# Advertisement_Matrix.net
KiCad netlist of a schematic drawn in EAGLE
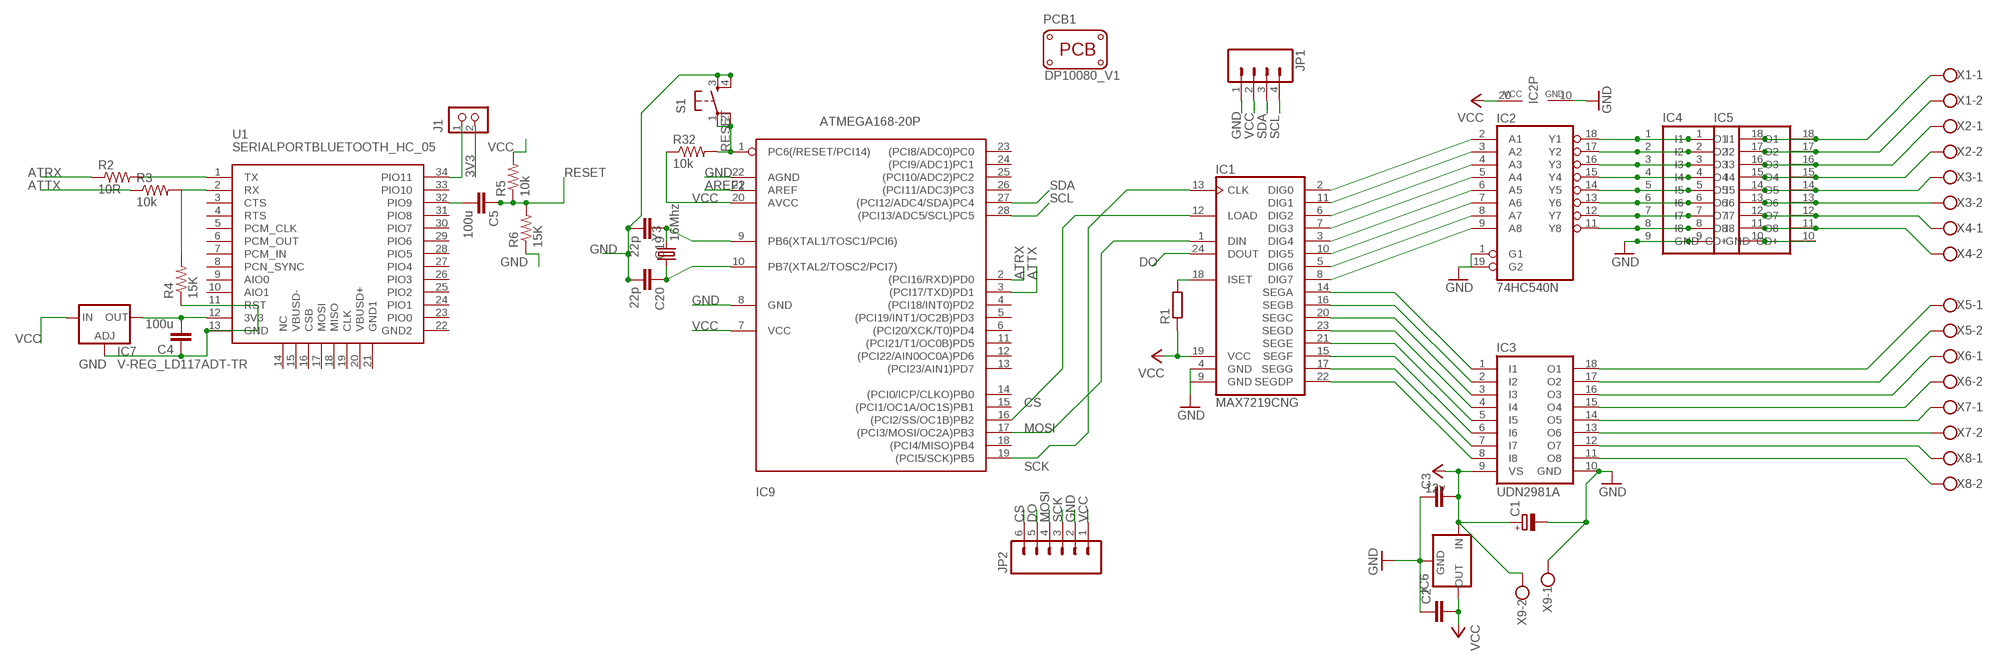
[diagram p0: schematic, sheet 1]

(export (version "E")
  (design (tool "Eeschema 10.0.6"))
  (components
    (comp (ref "C1")
      (value "CPOL-EUE2.5-7")
      (footprint "eagle-import:E2,5-7")
      (libsource (lib "eagle-import") (part "CPOL-EUE2.5-7"))
    )
    (comp (ref "C2")
      (value "C-EUC1206K")
      (footprint "eagle-import:C1206K")
      (libsource (lib "eagle-import") (part "C-EUC1206K"))
    )
    (comp (ref "C3")
      (value "C-EUC1206K")
      (footprint "eagle-import:C1206K")
      (libsource (lib "eagle-import") (part "C-EUC1206K"))
    )
    (comp (ref "C4")
      (value "100u")
      (footprint "eagle-import:1206")
      (libsource (lib "eagle-import") (part "CAP1206"))
    )
    (comp (ref "C5")
      (value "100u")
      (footprint "eagle-import:1206")
      (libsource (lib "eagle-import") (part "CAP1206"))
    )
    (comp (ref "C19")
      (value "22p")
      (footprint "eagle-import:1206")
      (libsource (lib "eagle-import") (part "CAP1206"))
    )
    (comp (ref "C20")
      (value "22p")
      (footprint "eagle-import:1206")
      (libsource (lib "eagle-import") (part "CAP1206"))
    )
    (comp (ref "IC1")
      (value "MAX7219CNG")
      (footprint "eagle-import:DIL24-3")
      (fields (field (name "MF") "MAXIM"))
      (libsource (lib "eagle-import") (part "MAX7219CNG"))
    )
    (comp (ref "IC2")
      (value "74HC540N")
      (footprint "eagle-import:DIL20")
      (libsource (lib "eagle-import") (part "74540NHC"))
    )
    (comp (ref "IC3")
      (value "UDN2981A")
      (footprint "eagle-import:DIL18")
      (libsource (lib "eagle-import") (part "UDN298A1"))
    )
    (comp (ref "IC4")
      (value "IC_ULN2803AN")
      (footprint "eagle-import:DIL18")
      (libsource (lib "eagle-import") (part "IC_ULN2803AN"))
    )
    (comp (ref "IC5")
      (value "IC_ULN2803AN")
      (footprint "eagle-import:DIL18")
      (libsource (lib "eagle-import") (part "IC_ULN2803AN"))
    )
    (comp (ref "IC6")
      (value "78XXL")
      (footprint "eagle-import:78XXL")
      (libsource (lib "eagle-import") (part "78XXL"))
    )
    (comp (ref "IC7")
      (value "V-REG_LD117ADT-TR")
      (footprint "eagle-import:V-REG_DPACK")
      (libsource (lib "eagle-import") (part "V-REG_LD117A?DT-TR"))
    )
    (comp (ref "IC9")
      (value "ATMEGA168-20P")
      (footprint "eagle-import:DIL28-3")
      (libsource (lib "eagle-import") (part "ATMEGA168P-20"))
    )
    (comp (ref "J1")
      (value "CON_HEADER_1X02-PTH")
      (footprint "eagle-import:M1X2")
      (libsource (lib "eagle-import") (part "CON_HEADER_1X02-PTH"))
    )
    (comp (ref "JP1")
      (value "M04POLAR_LOCK")
      (footprint "eagle-import:MOLEX-1X4_LOCK")
      (libsource (lib "eagle-import") (part "M04POLAR_LOCK"))
    )
    (comp (ref "JP2")
      (value "M06POLAR_LOCK")
      (footprint "eagle-import:MOLEX-1X6_LOCK")
      (libsource (lib "eagle-import") (part "M06POLAR_LOCK"))
    )
    (comp (ref "PCB1")
      (value "PCB_DP_RECTANGLE-80X100")
      (footprint "eagle-import:DP10080_V1")
      (libsource (lib "eagle-import") (part "PCB_DP_RECTANGLE-80X100"))
    )
    (comp (ref "R1")
      (value "R-EU_0207/7")
      (footprint "eagle-import:0207_7")
      (libsource (lib "eagle-import") (part "R-EU_0207/7"))
    )
    (comp (ref "R2")
      (value "10R")
      (footprint "eagle-import:M1206")
      (libsource (lib "eagle-import") (part "R-US_M1206"))
    )
    (comp (ref "R3")
      (value "10k")
      (footprint "eagle-import:M1206")
      (libsource (lib "eagle-import") (part "R-US_M1206"))
    )
    (comp (ref "R4")
      (value "15K")
      (footprint "eagle-import:M1206")
      (libsource (lib "eagle-import") (part "R-US_M1206"))
    )
    (comp (ref "R5")
      (value "10k")
      (footprint "eagle-import:M1206")
      (libsource (lib "eagle-import") (part "R-US_M1206"))
    )
    (comp (ref "R6")
      (value "15K")
      (footprint "eagle-import:M1206")
      (libsource (lib "eagle-import") (part "R-US_M1206"))
    )
    (comp (ref "R32")
      (value "10k")
      (footprint "eagle-import:M1206")
      (libsource (lib "eagle-import") (part "R-US_M1206"))
    )
    (comp (ref "S1")
      (value "TAC_SWITCHPTH")
      (footprint "eagle-import:TACTILE-PTH")
      (libsource (lib "eagle-import") (part "TAC_SWITCHPTH"))
    )
    (comp (ref "U1")
      (value "SERIALPORTBLUETOOTH_HC_05")
      (footprint "eagle-import:SERIALPORTBLUETOOTH_BLUETOOTH_SMD")
      (libsource (lib "eagle-import") (part "SERIALPORTBLUETOOTH_HC_05"))
    )
    (comp (ref "X1")
      (value "W237-102")
      (footprint "eagle-import:W237-102")
      (fields (field (name "MPN") "237-102"))
      (libsource (lib "eagle-import") (part "W237-102"))
    )
    (comp (ref "X2")
      (value "W237-102")
      (footprint "eagle-import:W237-102")
      (fields (field (name "MPN") "237-102"))
      (libsource (lib "eagle-import") (part "W237-102"))
    )
    (comp (ref "X3")
      (value "W237-102")
      (footprint "eagle-import:W237-102")
      (fields (field (name "MPN") "237-102"))
      (libsource (lib "eagle-import") (part "W237-102"))
    )
    (comp (ref "X4")
      (value "W237-102")
      (footprint "eagle-import:W237-102")
      (fields (field (name "MPN") "237-102"))
      (libsource (lib "eagle-import") (part "W237-102"))
    )
    (comp (ref "X5")
      (value "W237-102")
      (footprint "eagle-import:W237-102")
      (fields (field (name "MPN") "237-102"))
      (libsource (lib "eagle-import") (part "W237-102"))
    )
    (comp (ref "X6")
      (value "W237-102")
      (footprint "eagle-import:W237-102")
      (fields (field (name "MPN") "237-102"))
      (libsource (lib "eagle-import") (part "W237-102"))
    )
    (comp (ref "X7")
      (value "W237-102")
      (footprint "eagle-import:W237-102")
      (fields (field (name "MPN") "237-102"))
      (libsource (lib "eagle-import") (part "W237-102"))
    )
    (comp (ref "X8")
      (value "W237-102")
      (footprint "eagle-import:W237-102")
      (fields (field (name "MPN") "237-102"))
      (libsource (lib "eagle-import") (part "W237-102"))
    )
    (comp (ref "X9")
      (value "W237-102")
      (footprint "eagle-import:W237-102")
      (fields (field (name "MPN") "237-102"))
      (libsource (lib "eagle-import") (part "W237-102"))
    )
    (comp (ref "Y3")
      (value "16Mhz")
      (footprint "eagle-import:HC49UP")
      (libsource (lib "eagle-import") (part "CRYSTALSMD"))
    )
  )
  (nets
    (net (code "1") (name "/3V3") (class "Default")
      (node (ref "C4") (pin "2") (pinfunction "2_2") (pintype "passive"))
      (node (ref "IC7") (pin "4") (pinfunction "OUT_4") (pintype "passive"))
      (node (ref "J1") (pin "2") (pinfunction "2_2") (pintype "passive"))
      (node (ref "U1") (pin "12") (pinfunction "3V3_12") (pintype "bidirectional"))
    )
    (net (code "2") (name "/AREF2") (class "Default")
      (node (ref "IC9") (pin "21") (pinfunction "AREF_21") (pintype "bidirectional"))
    )
    (net (code "3") (name "/ATRX") (class "Default")
      (node (ref "IC9") (pin "2") (pinfunction "(PCI16/RXD)PD0_2") (pintype "bidirectional"))
      (node (ref "R2") (pin "1") (pinfunction "1_1") (pintype "passive"))
    )
    (net (code "4") (name "/ATTX") (class "Default")
      (node (ref "IC9") (pin "3") (pinfunction "(PCI17/TXD)PD1_3") (pintype "bidirectional"))
      (node (ref "R3") (pin "1") (pinfunction "1_1") (pintype "passive"))
    )
    (net (code "5") (name "/CS") (class "Default")
      (node (ref "IC1") (pin "12") (pinfunction "LOAD_12") (pintype "input"))
      (node (ref "IC9") (pin "16") (pinfunction "(PCI2/SS/OC1B)PB2_16") (pintype "bidirectional"))
      (node (ref "JP2") (pin "6") (pinfunction "6_6") (pintype "passive"))
    )
    (net (code "6") (name "/DO") (class "Default")
      (node (ref "IC1") (pin "24") (pinfunction "DOUT_24") (pintype "output"))
      (node (ref "JP2") (pin "5") (pinfunction "5_5") (pintype "passive"))
    )
    (net (code "7") (name "/MOSI") (class "Default")
      (node (ref "IC1") (pin "1") (pinfunction "DIN_1") (pintype "input"))
      (node (ref "IC9") (pin "17") (pinfunction "(PCI3/MOSI/OC2A)PB3_17") (pintype "bidirectional"))
      (node (ref "JP2") (pin "4") (pinfunction "4_4") (pintype "passive"))
    )
    (net (code "8") (name "/RESET") (class "Default")
      (node (ref "C5") (pin "1") (pinfunction "1_1") (pintype "passive"))
      (node (ref "IC9") (pin "1") (pinfunction "PC6(/RESET/PCI14)_1") (pintype "bidirectional"))
      (node (ref "R32") (pin "2") (pinfunction "2_2") (pintype "passive"))
      (node (ref "R5") (pin "1") (pinfunction "1_1") (pintype "passive"))
      (node (ref "R6") (pin "2") (pinfunction "2_2") (pintype "passive"))
      (node (ref "S1") (pin "1") (pinfunction "1_1") (pintype "passive"))
      (node (ref "S1") (pin "2") (pinfunction "2_2") (pintype "passive"))
    )
    (net (code "9") (name "/SCK") (class "Default")
      (node (ref "IC1") (pin "13") (pinfunction "CLK_13") (pintype "input"))
      (node (ref "IC9") (pin "19") (pinfunction "(PCI5/SCK)PB5_19") (pintype "bidirectional"))
      (node (ref "JP2") (pin "3") (pinfunction "3_3") (pintype "passive"))
    )
    (net (code "10") (name "/SCL") (class "Default")
      (node (ref "IC9") (pin "28") (pinfunction "(PCI13/ADC5/SCL)PC5_28") (pintype "bidirectional"))
      (node (ref "JP1") (pin "4") (pinfunction "4_4") (pintype "passive"))
    )
    (net (code "11") (name "/SDA") (class "Default")
      (node (ref "IC9") (pin "27") (pinfunction "(PCI12/ADC4/SDA)PC4_27") (pintype "bidirectional"))
      (node (ref "JP1") (pin "3") (pinfunction "3_3") (pintype "passive"))
    )
    (net (code "12") (name "12v") (class "Default")
      (node (ref "C1") (pin "+") (pinfunction "+_+") (pintype "passive"))
      (node (ref "C3") (pin "2") (pinfunction "2_2") (pintype "passive"))
      (node (ref "IC3") (pin "9") (pinfunction "VS_9") (pintype "passive"))
      (node (ref "IC6") (pin "IN") (pinfunction "IN_IN") (pintype "input"))
      (node (ref "X9") (pin "2") (pinfunction "KL_2") (pintype "passive"))
    )
    (net (code "13") (name "GND") (class "Default")
      (node (ref "C1") (pin "-") (pinfunction "-_-") (pintype "passive"))
      (node (ref "C19") (pin "2") (pinfunction "2_2") (pintype "passive"))
      (node (ref "C2") (pin "1") (pinfunction "1_1") (pintype "passive"))
      (node (ref "C20") (pin "2") (pinfunction "2_2") (pintype "passive"))
      (node (ref "C3") (pin "1") (pinfunction "1_1") (pintype "passive"))
      (node (ref "C4") (pin "1") (pinfunction "1_1") (pintype "passive"))
      (node (ref "IC1") (pin "4") (pinfunction "GND_4") (pintype "power_in"))
      (node (ref "IC1") (pin "9") (pinfunction "GND_9") (pintype "power_in"))
      (node (ref "IC2") (pin "1") (pinfunction "G1_1") (pintype "input"))
      (node (ref "IC2") (pin "10") (pinfunction "GND_10") (pintype "power_in"))
      (node (ref "IC2") (pin "19") (pinfunction "G2_19") (pintype "input"))
      (node (ref "IC3") (pin "10") (pinfunction "GND_10") (pintype "power_in"))
      (node (ref "IC4") (pin "9") (pinfunction "GND_9") (pintype "power_in"))
      (node (ref "IC5") (pin "9") (pinfunction "GND_9") (pintype "power_in"))
      (node (ref "IC6") (pin "GND") (pinfunction "GND_GND") (pintype "input"))
      (node (ref "IC7") (pin "1") (pinfunction "ADJ_1") (pintype "input"))
      (node (ref "IC9") (pin "22") (pinfunction "AGND_22") (pintype "bidirectional"))
      (node (ref "IC9") (pin "8") (pinfunction "GND_8") (pintype "bidirectional"))
      (node (ref "JP1") (pin "1") (pinfunction "1_1") (pintype "passive"))
      (node (ref "JP2") (pin "2") (pinfunction "2_2") (pintype "passive"))
      (node (ref "R4") (pin "1") (pinfunction "1_1") (pintype "passive"))
      (node (ref "R6") (pin "1") (pinfunction "1_1") (pintype "passive"))
      (node (ref "S1") (pin "3") (pinfunction "3_3") (pintype "passive"))
      (node (ref "S1") (pin "4") (pinfunction "4_4") (pintype "passive"))
      (node (ref "U1") (pin "13") (pinfunction "GND_13") (pintype "bidirectional"))
      (node (ref "X9") (pin "1") (pinfunction "KL_1") (pintype "passive"))
    )
    (net (code "14") (name "Net-(IC1-DIG0)") (class "Default")
      (node (ref "IC1") (pin "2") (pinfunction "DIG0_2") (pintype "output"))
      (node (ref "IC2") (pin "2") (pinfunction "A1_2") (pintype "input"))
    )
    (net (code "15") (name "Net-(IC1-DIG1)") (class "Default")
      (node (ref "IC1") (pin "11") (pinfunction "DIG1_11") (pintype "output"))
      (node (ref "IC2") (pin "3") (pinfunction "A2_3") (pintype "input"))
    )
    (net (code "16") (name "Net-(IC1-DIG2)") (class "Default")
      (node (ref "IC1") (pin "6") (pinfunction "DIG2_6") (pintype "output"))
      (node (ref "IC2") (pin "4") (pinfunction "A3_4") (pintype "input"))
    )
    (net (code "17") (name "Net-(IC1-DIG3)") (class "Default")
      (node (ref "IC1") (pin "7") (pinfunction "DIG3_7") (pintype "output"))
      (node (ref "IC2") (pin "5") (pinfunction "A4_5") (pintype "input"))
    )
    (net (code "18") (name "Net-(IC1-DIG4)") (class "Default")
      (node (ref "IC1") (pin "3") (pinfunction "DIG4_3") (pintype "output"))
      (node (ref "IC2") (pin "6") (pinfunction "A5_6") (pintype "input"))
    )
    (net (code "19") (name "Net-(IC1-DIG5)") (class "Default")
      (node (ref "IC1") (pin "10") (pinfunction "DIG5_10") (pintype "output"))
      (node (ref "IC2") (pin "7") (pinfunction "A6_7") (pintype "input"))
    )
    (net (code "20") (name "Net-(IC1-DIG6)") (class "Default")
      (node (ref "IC1") (pin "5") (pinfunction "DIG6_5") (pintype "output"))
      (node (ref "IC2") (pin "8") (pinfunction "A7_8") (pintype "input"))
    )
    (net (code "21") (name "Net-(IC1-DIG7)") (class "Default")
      (node (ref "IC1") (pin "8") (pinfunction "DIG7_8") (pintype "output"))
      (node (ref "IC2") (pin "9") (pinfunction "A8_9") (pintype "input"))
    )
    (net (code "22") (name "Net-(IC1-ISET)") (class "Default")
      (node (ref "IC1") (pin "18") (pinfunction "ISET_18") (pintype "input"))
      (node (ref "R1") (pin "2") (pinfunction "2_2") (pintype "passive"))
    )
    (net (code "23") (name "Net-(IC1-SEGA)") (class "Default")
      (node (ref "IC1") (pin "14") (pinfunction "SEGA_14") (pintype "output"))
      (node (ref "IC3") (pin "1") (pinfunction "I1_1") (pintype "input"))
    )
    (net (code "24") (name "Net-(IC1-SEGB)") (class "Default")
      (node (ref "IC1") (pin "16") (pinfunction "SEGB_16") (pintype "output"))
      (node (ref "IC3") (pin "2") (pinfunction "I2_2") (pintype "input"))
    )
    (net (code "25") (name "Net-(IC1-SEGC)") (class "Default")
      (node (ref "IC1") (pin "20") (pinfunction "SEGC_20") (pintype "output"))
      (node (ref "IC3") (pin "3") (pinfunction "I3_3") (pintype "input"))
    )
    (net (code "26") (name "Net-(IC1-SEGD)") (class "Default")
      (node (ref "IC1") (pin "23") (pinfunction "SEGD_23") (pintype "output"))
      (node (ref "IC3") (pin "4") (pinfunction "I4_4") (pintype "input"))
    )
    (net (code "27") (name "Net-(IC1-SEGDP)") (class "Default")
      (node (ref "IC1") (pin "22") (pinfunction "SEGDP_22") (pintype "output"))
      (node (ref "IC3") (pin "8") (pinfunction "I8_8") (pintype "input"))
    )
    (net (code "28") (name "Net-(IC1-SEGE)") (class "Default")
      (node (ref "IC1") (pin "21") (pinfunction "SEGE_21") (pintype "output"))
      (node (ref "IC3") (pin "5") (pinfunction "I5_5") (pintype "input"))
    )
    (net (code "29") (name "Net-(IC1-SEGF)") (class "Default")
      (node (ref "IC1") (pin "15") (pinfunction "SEGF_15") (pintype "output"))
      (node (ref "IC3") (pin "6") (pinfunction "I6_6") (pintype "input"))
    )
    (net (code "30") (name "Net-(IC1-SEGG)") (class "Default")
      (node (ref "IC1") (pin "17") (pinfunction "SEGG_17") (pintype "output"))
      (node (ref "IC3") (pin "7") (pinfunction "I7_7") (pintype "input"))
    )
    (net (code "31") (name "Net-(IC2A-Y1)") (class "Default")
      (node (ref "IC2") (pin "18") (pinfunction "Y1_18") (pintype "tri_state"))
      (node (ref "IC4") (pin "1") (pinfunction "I1_1") (pintype "input"))
      (node (ref "IC5") (pin "1") (pinfunction "I1_1") (pintype "input"))
    )
    (net (code "32") (name "Net-(IC2A-Y2)") (class "Default")
      (node (ref "IC2") (pin "17") (pinfunction "Y2_17") (pintype "tri_state"))
      (node (ref "IC4") (pin "2") (pinfunction "I2_2") (pintype "input"))
      (node (ref "IC5") (pin "2") (pinfunction "I2_2") (pintype "input"))
    )
    (net (code "33") (name "Net-(IC2A-Y3)") (class "Default")
      (node (ref "IC2") (pin "16") (pinfunction "Y3_16") (pintype "tri_state"))
      (node (ref "IC4") (pin "3") (pinfunction "I3_3") (pintype "input"))
      (node (ref "IC5") (pin "3") (pinfunction "I3_3") (pintype "input"))
    )
    (net (code "34") (name "Net-(IC2A-Y4)") (class "Default")
      (node (ref "IC2") (pin "15") (pinfunction "Y4_15") (pintype "tri_state"))
      (node (ref "IC4") (pin "4") (pinfunction "I4_4") (pintype "input"))
      (node (ref "IC5") (pin "4") (pinfunction "I4_4") (pintype "input"))
    )
    (net (code "35") (name "Net-(IC2A-Y5)") (class "Default")
      (node (ref "IC2") (pin "14") (pinfunction "Y5_14") (pintype "tri_state"))
      (node (ref "IC4") (pin "5") (pinfunction "I5_5") (pintype "input"))
      (node (ref "IC5") (pin "5") (pinfunction "I5_5") (pintype "input"))
    )
    (net (code "36") (name "Net-(IC2A-Y6)") (class "Default")
      (node (ref "IC2") (pin "13") (pinfunction "Y6_13") (pintype "tri_state"))
      (node (ref "IC4") (pin "6") (pinfunction "I6_6") (pintype "input"))
      (node (ref "IC5") (pin "6") (pinfunction "I6_6") (pintype "input"))
    )
    (net (code "37") (name "Net-(IC2A-Y7)") (class "Default")
      (node (ref "IC2") (pin "12") (pinfunction "Y7_12") (pintype "tri_state"))
      (node (ref "IC4") (pin "7") (pinfunction "I7_7") (pintype "input"))
      (node (ref "IC5") (pin "7") (pinfunction "I7_7") (pintype "input"))
    )
    (net (code "38") (name "Net-(IC2A-Y8)") (class "Default")
      (node (ref "IC2") (pin "11") (pinfunction "Y8_11") (pintype "tri_state"))
      (node (ref "IC4") (pin "8") (pinfunction "I8_8") (pintype "input"))
      (node (ref "IC5") (pin "8") (pinfunction "I8_8") (pintype "input"))
    )
    (net (code "39") (name "Net-(IC3-O1)") (class "Default")
      (node (ref "IC3") (pin "18") (pinfunction "O1_18") (pintype "open_collector"))
      (node (ref "X5") (pin "1") (pinfunction "KL_1") (pintype "passive"))
    )
    (net (code "40") (name "Net-(IC3-O2)") (class "Default")
      (node (ref "IC3") (pin "17") (pinfunction "O2_17") (pintype "open_collector"))
      (node (ref "X5") (pin "2") (pinfunction "KL_2") (pintype "passive"))
    )
    (net (code "41") (name "Net-(IC3-O3)") (class "Default")
      (node (ref "IC3") (pin "16") (pinfunction "O3_16") (pintype "open_collector"))
      (node (ref "X6") (pin "1") (pinfunction "KL_1") (pintype "passive"))
    )
    (net (code "42") (name "Net-(IC3-O4)") (class "Default")
      (node (ref "IC3") (pin "15") (pinfunction "O4_15") (pintype "open_collector"))
      (node (ref "X6") (pin "2") (pinfunction "KL_2") (pintype "passive"))
    )
    (net (code "43") (name "Net-(IC3-O5)") (class "Default")
      (node (ref "IC3") (pin "14") (pinfunction "O5_14") (pintype "open_collector"))
      (node (ref "X7") (pin "1") (pinfunction "KL_1") (pintype "passive"))
    )
    (net (code "44") (name "Net-(IC3-O6)") (class "Default")
      (node (ref "IC3") (pin "13") (pinfunction "O6_13") (pintype "open_collector"))
      (node (ref "X7") (pin "2") (pinfunction "KL_2") (pintype "passive"))
    )
    (net (code "45") (name "Net-(IC3-O7)") (class "Default")
      (node (ref "IC3") (pin "12") (pinfunction "O7_12") (pintype "open_collector"))
      (node (ref "X8") (pin "1") (pinfunction "KL_1") (pintype "passive"))
    )
    (net (code "46") (name "Net-(IC3-O8)") (class "Default")
      (node (ref "IC3") (pin "11") (pinfunction "O8_11") (pintype "open_collector"))
      (node (ref "X8") (pin "2") (pinfunction "KL_2") (pintype "passive"))
    )
    (net (code "47") (name "Net-(IC4-CD+)") (class "Default")
      (node (ref "IC4") (pin "10") (pinfunction "CD+_10") (pintype "passive"))
      (node (ref "IC5") (pin "10") (pinfunction "CD+_10") (pintype "passive"))
    )
    (net (code "48") (name "Net-(IC4-O1)") (class "Default")
      (node (ref "IC4") (pin "18") (pinfunction "O1_18") (pintype "open_collector"))
      (node (ref "IC5") (pin "18") (pinfunction "O1_18") (pintype "open_collector"))
      (node (ref "X1") (pin "1") (pinfunction "KL_1") (pintype "passive"))
    )
    (net (code "49") (name "Net-(IC4-O2)") (class "Default")
      (node (ref "IC4") (pin "17") (pinfunction "O2_17") (pintype "open_collector"))
      (node (ref "IC5") (pin "17") (pinfunction "O2_17") (pintype "open_collector"))
      (node (ref "X1") (pin "2") (pinfunction "KL_2") (pintype "passive"))
    )
    (net (code "50") (name "Net-(IC4-O3)") (class "Default")
      (node (ref "IC4") (pin "16") (pinfunction "O3_16") (pintype "open_collector"))
      (node (ref "IC5") (pin "16") (pinfunction "O3_16") (pintype "open_collector"))
      (node (ref "X2") (pin "1") (pinfunction "KL_1") (pintype "passive"))
    )
    (net (code "51") (name "Net-(IC4-O4)") (class "Default")
      (node (ref "IC4") (pin "15") (pinfunction "O4_15") (pintype "open_collector"))
      (node (ref "IC5") (pin "15") (pinfunction "O4_15") (pintype "open_collector"))
      (node (ref "X2") (pin "2") (pinfunction "KL_2") (pintype "passive"))
    )
    (net (code "52") (name "Net-(IC4-O5)") (class "Default")
      (node (ref "IC4") (pin "14") (pinfunction "O5_14") (pintype "open_collector"))
      (node (ref "IC5") (pin "14") (pinfunction "O5_14") (pintype "open_collector"))
      (node (ref "X3") (pin "1") (pinfunction "KL_1") (pintype "passive"))
    )
    (net (code "53") (name "Net-(IC4-O6)") (class "Default")
      (node (ref "IC4") (pin "13") (pinfunction "O6_13") (pintype "open_collector"))
      (node (ref "IC5") (pin "13") (pinfunction "O6_13") (pintype "open_collector"))
      (node (ref "X3") (pin "2") (pinfunction "KL_2") (pintype "passive"))
    )
    (net (code "54") (name "Net-(IC4-O7)") (class "Default")
      (node (ref "IC4") (pin "12") (pinfunction "O7_12") (pintype "open_collector"))
      (node (ref "IC5") (pin "12") (pinfunction "O7_12") (pintype "open_collector"))
      (node (ref "X4") (pin "1") (pinfunction "KL_1") (pintype "passive"))
    )
    (net (code "55") (name "Net-(IC4-O8)") (class "Default")
      (node (ref "IC4") (pin "11") (pinfunction "O8_11") (pintype "open_collector"))
      (node (ref "IC5") (pin "11") (pinfunction "O8_11") (pintype "open_collector"))
      (node (ref "X4") (pin "2") (pinfunction "KL_2") (pintype "passive"))
    )
    (net (code "56") (name "Net-(IC9-PB6(XTAL1{slash}TOSC1{slash}PCI6))") (class "Default")
      (node (ref "C19") (pin "1") (pinfunction "1_1") (pintype "passive"))
      (node (ref "IC9") (pin "9") (pinfunction "PB6(XTAL1/TOSC1/PCI6)_9") (pintype "bidirectional"))
      (node (ref "Y3") (pin "2") (pinfunction "2_2") (pintype "passive"))
    )
    (net (code "57") (name "Net-(IC9-PB7(XTAL2{slash}TOSC2{slash}PCI7))") (class "Default")
      (node (ref "C20") (pin "1") (pinfunction "1_1") (pintype "passive"))
      (node (ref "IC9") (pin "10") (pinfunction "PB7(XTAL2/TOSC2/PCI7)_10") (pintype "bidirectional"))
      (node (ref "Y3") (pin "1") (pinfunction "1_1") (pintype "passive"))
    )
    (net (code "58") (name "Net-(U1-PIO9)") (class "Default")
      (node (ref "C5") (pin "2") (pinfunction "2_2") (pintype "passive"))
      (node (ref "U1") (pin "32") (pinfunction "PIO9_32") (pintype "bidirectional"))
    )
    (net (code "59") (name "Net-(U1-PIO11)") (class "Default")
      (node (ref "J1") (pin "1") (pinfunction "1_1") (pintype "passive"))
      (node (ref "U1") (pin "34") (pinfunction "PIO11_34") (pintype "bidirectional"))
    )
    (net (code "60") (name "Net-(U1-RX)") (class "Default")
      (node (ref "R3") (pin "2") (pinfunction "2_2") (pintype "passive"))
      (node (ref "R4") (pin "2") (pinfunction "2_2") (pintype "passive"))
      (node (ref "U1") (pin "2") (pinfunction "RX_2") (pintype "bidirectional"))
    )
    (net (code "61") (name "Net-(U1-TX)") (class "Default")
      (node (ref "R2") (pin "2") (pinfunction "2_2") (pintype "passive"))
      (node (ref "U1") (pin "1") (pinfunction "TX_1") (pintype "bidirectional"))
    )
    (net (code "62") (name "VCC") (class "Default")
      (node (ref "C2") (pin "2") (pinfunction "2_2") (pintype "passive"))
      (node (ref "IC1") (pin "19") (pinfunction "VCC_19") (pintype "power_in"))
      (node (ref "IC2") (pin "20") (pinfunction "VCC_20") (pintype "power_in"))
      (node (ref "IC6") (pin "OUT") (pinfunction "OUT_OUT") (pintype "passive"))
      (node (ref "IC7") (pin "3") (pinfunction "IN_3") (pintype "input"))
      (node (ref "IC9") (pin "20") (pinfunction "AVCC_20") (pintype "bidirectional"))
      (node (ref "IC9") (pin "7") (pinfunction "VCC_7") (pintype "bidirectional"))
      (node (ref "JP1") (pin "2") (pinfunction "2_2") (pintype "passive"))
      (node (ref "JP2") (pin "1") (pinfunction "1_1") (pintype "passive"))
      (node (ref "R1") (pin "1") (pinfunction "1_1") (pintype "passive"))
      (node (ref "R32") (pin "1") (pinfunction "1_1") (pintype "passive"))
      (node (ref "R5") (pin "2") (pinfunction "2_2") (pintype "passive"))
    )
    (net (code "63") (name "unconnected-(IC9-(PCI0{slash}ICP{slash}CLKO)PB0-Pad14)") (class "Default")
      (node (ref "IC9") (pin "14") (pinfunction "(PCI0/ICP/CLKO)PB0_14") (pintype "bidirectional"))
    )
    (net (code "64") (name "unconnected-(IC9-(PCI1{slash}OC1A{slash}OC1S)PB1-Pad15)") (class "Default")
      (node (ref "IC9") (pin "15") (pinfunction "(PCI1/OC1A/OC1S)PB1_15") (pintype "bidirectional"))
    )
    (net (code "65") (name "unconnected-(IC9-(PCI4{slash}MISO)PB4-Pad18)") (class "Default")
      (node (ref "IC9") (pin "18") (pinfunction "(PCI4/MISO)PB4_18") (pintype "bidirectional"))
    )
    (net (code "66") (name "unconnected-(IC9-(PCI8{slash}ADC0)PC0-Pad23)") (class "Default")
      (node (ref "IC9") (pin "23") (pinfunction "(PCI8/ADC0)PC0_23") (pintype "bidirectional"))
    )
    (net (code "67") (name "unconnected-(IC9-(PCI9{slash}ADC1)PC1-Pad24)") (class "Default")
      (node (ref "IC9") (pin "24") (pinfunction "(PCI9/ADC1)PC1_24") (pintype "bidirectional"))
    )
    (net (code "68") (name "unconnected-(IC9-(PCI10{slash}ADC2)PC2-Pad25)") (class "Default")
      (node (ref "IC9") (pin "25") (pinfunction "(PCI10/ADC2)PC2_25") (pintype "bidirectional"))
    )
    (net (code "69") (name "unconnected-(IC9-(PCI11{slash}ADC3)PC3-Pad26)") (class "Default")
      (node (ref "IC9") (pin "26") (pinfunction "(PCI11/ADC3)PC3_26") (pintype "bidirectional"))
    )
    (net (code "70") (name "unconnected-(IC9-(PCI18{slash}INT0)PD2-Pad4)") (class "Default")
      (node (ref "IC9") (pin "4") (pinfunction "(PCI18/INT0)PD2_4") (pintype "bidirectional"))
    )
    (net (code "71") (name "unconnected-(IC9-(PCI19{slash}INT1{slash}OC2B)PD3-Pad5)") (class "Default")
      (node (ref "IC9") (pin "5") (pinfunction "(PCI19/INT1/OC2B)PD3_5") (pintype "bidirectional"))
    )
    (net (code "72") (name "unconnected-(IC9-(PCI20{slash}XCK{slash}T0)PD4-Pad6)") (class "Default")
      (node (ref "IC9") (pin "6") (pinfunction "(PCI20/XCK/T0)PD4_6") (pintype "bidirectional"))
    )
    (net (code "73") (name "unconnected-(IC9-(PCI21{slash}T1{slash}OC0B)PD5-Pad11)") (class "Default")
      (node (ref "IC9") (pin "11") (pinfunction "(PCI21/T1/OC0B)PD5_11") (pintype "bidirectional"))
    )
    (net (code "74") (name "unconnected-(IC9-(PCI22{slash}AIN0OC0A)PD6-Pad12)") (class "Default")
      (node (ref "IC9") (pin "12") (pinfunction "(PCI22/AIN0OC0A)PD6_12") (pintype "bidirectional"))
    )
    (net (code "75") (name "unconnected-(IC9-(PCI23{slash}AIN1)PD7-Pad13)") (class "Default")
      (node (ref "IC9") (pin "13") (pinfunction "(PCI23/AIN1)PD7_13") (pintype "bidirectional"))
    )
    (net (code "76") (name "unconnected-(U1-AIO0-Pad9)") (class "Default")
      (node (ref "U1") (pin "9") (pinfunction "AIO0_9") (pintype "bidirectional"))
    )
    (net (code "77") (name "unconnected-(U1-AIO1-Pad10)") (class "Default")
      (node (ref "U1") (pin "10") (pinfunction "AIO1_10") (pintype "bidirectional"))
    )
    (net (code "78") (name "unconnected-(U1-CLK-Pad19)") (class "Default")
      (node (ref "U1") (pin "19") (pinfunction "CLK_19") (pintype "bidirectional"))
    )
    (net (code "79") (name "unconnected-(U1-CSB-Pad16)") (class "Default")
      (node (ref "U1") (pin "16") (pinfunction "CSB_16") (pintype "bidirectional"))
    )
    (net (code "80") (name "unconnected-(U1-CTS-Pad3)") (class "Default")
      (node (ref "U1") (pin "3") (pinfunction "CTS_3") (pintype "bidirectional"))
    )
    (net (code "81") (name "unconnected-(U1-GND1-Pad21)") (class "Default")
      (node (ref "U1") (pin "21") (pinfunction "GND1_21") (pintype "bidirectional"))
    )
    (net (code "82") (name "unconnected-(U1-GND2-Pad22)") (class "Default")
      (node (ref "U1") (pin "22") (pinfunction "GND2_22") (pintype "bidirectional"))
    )
    (net (code "83") (name "unconnected-(U1-MISO-Pad18)") (class "Default")
      (node (ref "U1") (pin "18") (pinfunction "MISO_18") (pintype "bidirectional"))
    )
    (net (code "84") (name "unconnected-(U1-MOSI-Pad17)") (class "Default")
      (node (ref "U1") (pin "17") (pinfunction "MOSI_17") (pintype "bidirectional"))
    )
    (net (code "85") (name "unconnected-(U1-NC-Pad14)") (class "Default")
      (node (ref "U1") (pin "14") (pinfunction "NC_14") (pintype "bidirectional"))
    )
    (net (code "86") (name "unconnected-(U1-PCM_CLK-Pad5)") (class "Default")
      (node (ref "U1") (pin "5") (pinfunction "PCM_CLK_5") (pintype "bidirectional"))
    )
    (net (code "87") (name "unconnected-(U1-PCM_IN-Pad7)") (class "Default")
      (node (ref "U1") (pin "7") (pinfunction "PCM_IN_7") (pintype "bidirectional"))
    )
    (net (code "88") (name "unconnected-(U1-PCM_OUT-Pad6)") (class "Default")
      (node (ref "U1") (pin "6") (pinfunction "PCM_OUT_6") (pintype "bidirectional"))
    )
    (net (code "89") (name "unconnected-(U1-PCN_SYNC-Pad8)") (class "Default")
      (node (ref "U1") (pin "8") (pinfunction "PCN_SYNC_8") (pintype "bidirectional"))
    )
    (net (code "90") (name "unconnected-(U1-PIO0-Pad23)") (class "Default")
      (node (ref "U1") (pin "23") (pinfunction "PIO0_23") (pintype "bidirectional"))
    )
    (net (code "91") (name "unconnected-(U1-PIO1-Pad24)") (class "Default")
      (node (ref "U1") (pin "24") (pinfunction "PIO1_24") (pintype "bidirectional"))
    )
    (net (code "92") (name "unconnected-(U1-PIO2-Pad25)") (class "Default")
      (node (ref "U1") (pin "25") (pinfunction "PIO2_25") (pintype "bidirectional"))
    )
    (net (code "93") (name "unconnected-(U1-PIO3-Pad26)") (class "Default")
      (node (ref "U1") (pin "26") (pinfunction "PIO3_26") (pintype "bidirectional"))
    )
    (net (code "94") (name "unconnected-(U1-PIO4-Pad27)") (class "Default")
      (node (ref "U1") (pin "27") (pinfunction "PIO4_27") (pintype "bidirectional"))
    )
    (net (code "95") (name "unconnected-(U1-PIO5-Pad28)") (class "Default")
      (node (ref "U1") (pin "28") (pinfunction "PIO5_28") (pintype "bidirectional"))
    )
    (net (code "96") (name "unconnected-(U1-PIO6-Pad29)") (class "Default")
      (node (ref "U1") (pin "29") (pinfunction "PIO6_29") (pintype "bidirectional"))
    )
    (net (code "97") (name "unconnected-(U1-PIO7-Pad30)") (class "Default")
      (node (ref "U1") (pin "30") (pinfunction "PIO7_30") (pintype "bidirectional"))
    )
    (net (code "98") (name "unconnected-(U1-PIO8-Pad31)") (class "Default")
      (node (ref "U1") (pin "31") (pinfunction "PIO8_31") (pintype "bidirectional"))
    )
    (net (code "99") (name "unconnected-(U1-PIO10-Pad33)") (class "Default")
      (node (ref "U1") (pin "33") (pinfunction "PIO10_33") (pintype "bidirectional"))
    )
    (net (code "100") (name "unconnected-(U1-RST-Pad11)") (class "Default")
      (node (ref "U1") (pin "11") (pinfunction "RST_11") (pintype "bidirectional"))
    )
    (net (code "101") (name "unconnected-(U1-RTS-Pad4)") (class "Default")
      (node (ref "U1") (pin "4") (pinfunction "RTS_4") (pintype "bidirectional"))
    )
    (net (code "102") (name "unconnected-(U1-VBUSD+-Pad20)") (class "Default")
      (node (ref "U1") (pin "20") (pinfunction "VBUSD+_20") (pintype "bidirectional"))
    )
    (net (code "103") (name "unconnected-(U1-VBUSD--Pad15)") (class "Default")
      (node (ref "U1") (pin "15") (pinfunction "VBUSD-_15") (pintype "bidirectional"))
    )
  )
)
